# rev0.net
KiCad netlist of a schematic drawn in EAGLE
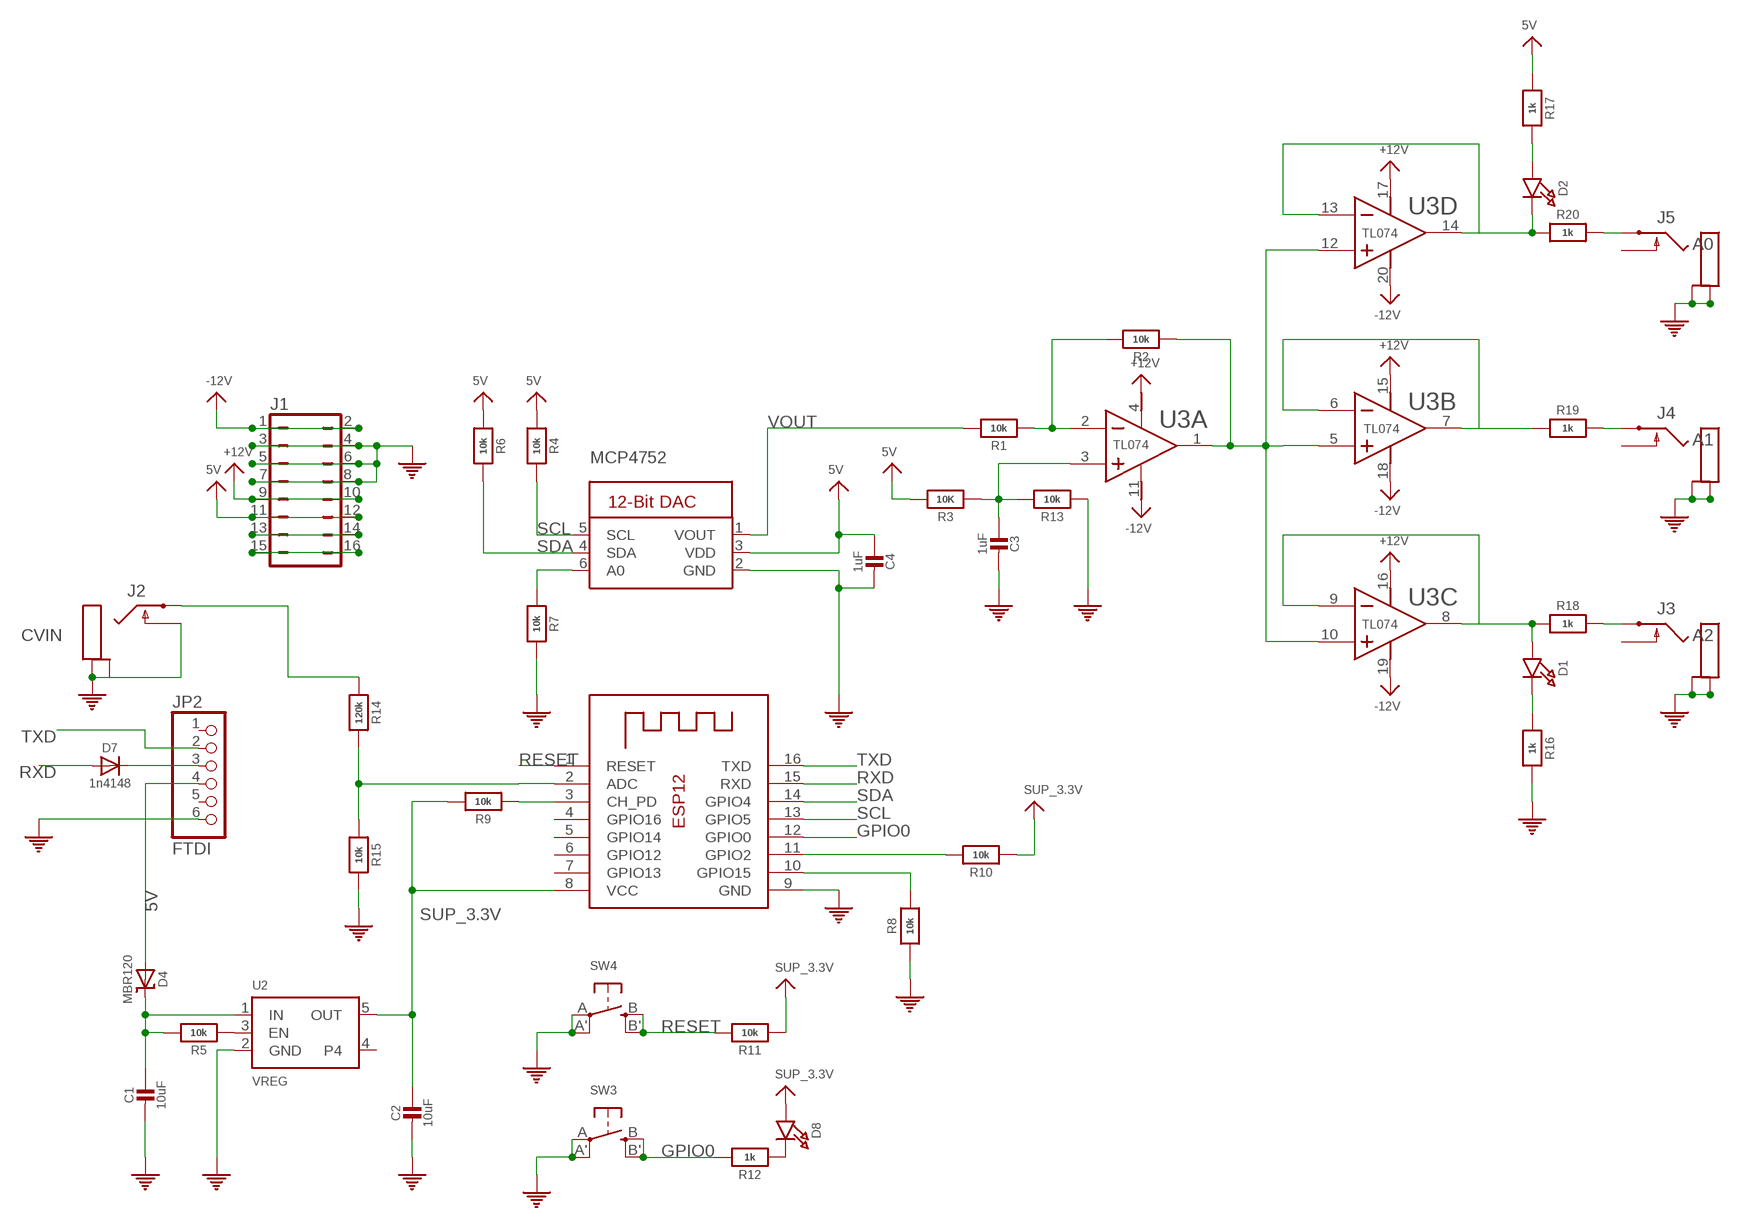
[diagram p0: schematic, sheet 1]

(export (version "E")
  (design (tool "Eeschema 10.0.6"))
  (components
    (comp (ref "C1")
      (value "10uF")
      (footprint "eagle-import:0805-NO")
      (libsource (lib "eagle-import") (part "CAP_CERAMIC0805-NOOUTLINE"))
    )
    (comp (ref "C2")
      (value "10uF")
      (footprint "eagle-import:0805-NO")
      (libsource (lib "eagle-import") (part "CAP_CERAMIC0805-NOOUTLINE"))
    )
    (comp (ref "C3")
      (value "1uF")
      (footprint "eagle-import:0805")
      (libsource (lib "eagle-import") (part "CAP_CERAMIC_0805"))
    )
    (comp (ref "C4")
      (value "1uF")
      (footprint "eagle-import:0805")
      (libsource (lib "eagle-import") (part "CAP_CERAMIC_0805"))
    )
    (comp (ref "D1")
      (value "LED0805_NOOUTLINE")
      (footprint "eagle-import:CHIPLED_0805_NOOUTLINE")
      (libsource (lib "eagle-import") (part "LED0805_NOOUTLINE"))
    )
    (comp (ref "D2")
      (value "LED0805_NOOUTLINE")
      (footprint "eagle-import:CHIPLED_0805_NOOUTLINE")
      (libsource (lib "eagle-import") (part "LED0805_NOOUTLINE"))
    )
    (comp (ref "D4")
      (value "MBR120")
      (footprint "eagle-import:SOD-123")
      (libsource (lib "eagle-import") (part "DIODE-SCHOTTKYSOD-123"))
    )
    (comp (ref "D7")
      (value "1n4148")
      (footprint "eagle-import:SOD-323")
      (libsource (lib "eagle-import") (part "DIODESOD-323"))
    )
    (comp (ref "D8")
      (value "LED0805_NOOUTLINE")
      (footprint "eagle-import:CHIPLED_0805_NOOUTLINE")
      (libsource (lib "eagle-import") (part "LED0805_NOOUTLINE"))
    )
    (comp (ref "J1")
      (value "JMP/16P/DIPDIP")
      (footprint "eagle-import:JMP_16P_DIP")
      (libsource (lib "eagle-import") (part "JMP/16P/DIPDIP"))
    )
    (comp (ref "J2")
      (value "1/8\"JACK/MONO/SWITCHED")
      (footprint "eagle-import:1_8_JACK_MONO_ERTHENVAR")
      (libsource (lib "eagle-import") (part "1/8{dblquote}JACK/MONO/SWITCHED"))
    )
    (comp (ref "J3")
      (value "1/8\"JACK/MONO/SWITCHED")
      (footprint "eagle-import:1_8_JACK_MONO_ERTHENVAR")
      (libsource (lib "eagle-import") (part "1/8{dblquote}JACK/MONO/SWITCHED"))
    )
    (comp (ref "J4")
      (value "1/8\"JACK/MONO/SWITCHED")
      (footprint "eagle-import:1_8_JACK_MONO_ERTHENVAR")
      (libsource (lib "eagle-import") (part "1/8{dblquote}JACK/MONO/SWITCHED"))
    )
    (comp (ref "J5")
      (value "1/8\"JACK/MONO/SWITCHED")
      (footprint "eagle-import:1_8_JACK_MONO_ERTHENVAR")
      (libsource (lib "eagle-import") (part "1/8{dblquote}JACK/MONO/SWITCHED"))
    )
    (comp (ref "JP2")
      (value "FTDI")
      (footprint "eagle-import:1X06_ROUND_70")
      (libsource (lib "eagle-import") (part "HEADER-1X670MIL"))
    )
    (comp (ref "MCP4752")
      (value "DAC_MCP4725")
      (footprint "eagle-import:SOT23-6")
      (libsource (lib "eagle-import") (part "DAC_MCP4725"))
    )
    (comp (ref "R1")
      (value "10k")
      (footprint "eagle-import:0805-NO")
      (libsource (lib "eagle-import") (part "RESISTOR0805_NOOUTLINE"))
    )
    (comp (ref "R2")
      (value "10k")
      (footprint "eagle-import:0805-NO")
      (libsource (lib "eagle-import") (part "RESISTOR0805_NOOUTLINE"))
    )
    (comp (ref "R3")
      (value "10K")
      (footprint "eagle-import:0805-NO")
      (libsource (lib "eagle-import") (part "RESISTOR0805_NOOUTLINE"))
    )
    (comp (ref "R4")
      (value "10k")
      (footprint "eagle-import:0805-NO")
      (libsource (lib "eagle-import") (part "RESISTOR0805_NOOUTLINE"))
    )
    (comp (ref "R5")
      (value "10k")
      (footprint "eagle-import:0805-NO")
      (libsource (lib "eagle-import") (part "RESISTOR0805_NOOUTLINE"))
    )
    (comp (ref "R6")
      (value "10k")
      (footprint "eagle-import:0805-NO")
      (libsource (lib "eagle-import") (part "RESISTOR0805_NOOUTLINE"))
    )
    (comp (ref "R7")
      (value "10k")
      (footprint "eagle-import:0805-NO")
      (libsource (lib "eagle-import") (part "RESISTOR0805_NOOUTLINE"))
    )
    (comp (ref "R8")
      (value "10k")
      (footprint "eagle-import:0805-NO")
      (libsource (lib "eagle-import") (part "RESISTOR0805_NOOUTLINE"))
    )
    (comp (ref "R9")
      (value "10k")
      (footprint "eagle-import:0805-NO")
      (libsource (lib "eagle-import") (part "RESISTOR0805_NOOUTLINE"))
    )
    (comp (ref "R10")
      (value "10k")
      (footprint "eagle-import:0805-NO")
      (libsource (lib "eagle-import") (part "RESISTOR0805_NOOUTLINE"))
    )
    (comp (ref "R11")
      (value "10k")
      (footprint "eagle-import:0805-NO")
      (libsource (lib "eagle-import") (part "RESISTOR0805_NOOUTLINE"))
    )
    (comp (ref "R12")
      (value "1k")
      (footprint "eagle-import:0805-NO")
      (libsource (lib "eagle-import") (part "RESISTOR0805_NOOUTLINE"))
    )
    (comp (ref "R13")
      (value "10k")
      (footprint "eagle-import:0805-NO")
      (libsource (lib "eagle-import") (part "RESISTOR0805_NOOUTLINE"))
    )
    (comp (ref "R14")
      (value "120k")
      (footprint "eagle-import:0805-NO")
      (libsource (lib "eagle-import") (part "RESISTOR0805_NOOUTLINE"))
    )
    (comp (ref "R15")
      (value "10k")
      (footprint "eagle-import:0805-NO")
      (libsource (lib "eagle-import") (part "RESISTOR0805_NOOUTLINE"))
    )
    (comp (ref "R16")
      (value "1k")
      (footprint "eagle-import:0805-NO")
      (libsource (lib "eagle-import") (part "RESISTOR0805_NOOUTLINE"))
    )
    (comp (ref "R17")
      (value "1k")
      (footprint "eagle-import:0805-NO")
      (libsource (lib "eagle-import") (part "RESISTOR0805_NOOUTLINE"))
    )
    (comp (ref "R18")
      (value "1k")
      (footprint "eagle-import:0805-NO")
      (libsource (lib "eagle-import") (part "RESISTOR0805_NOOUTLINE"))
    )
    (comp (ref "R19")
      (value "1k")
      (footprint "eagle-import:0805-NO")
      (libsource (lib "eagle-import") (part "RESISTOR0805_NOOUTLINE"))
    )
    (comp (ref "R20")
      (value "1k")
      (footprint "eagle-import:0805-NO")
      (libsource (lib "eagle-import") (part "RESISTOR0805_NOOUTLINE"))
    )
    (comp (ref "SW3")
      (value "SWITCH_TACT_SMT4.6X2.8")
      (footprint "eagle-import:BTN_KMR2_4.6X2.8")
      (libsource (lib "eagle-import") (part "SWITCH_TACT_SMT4.6X2.8"))
    )
    (comp (ref "SW4")
      (value "SWITCH_TACT_SMT4.6X2.8")
      (footprint "eagle-import:BTN_KMR2_4.6X2.8")
      (libsource (lib "eagle-import") (part "SWITCH_TACT_SMT4.6X2.8"))
    )
    (comp (ref "U2")
      (value "VREG")
      (footprint "eagle-import:SOT23-5")
      (libsource (lib "eagle-import") (part "VREG_SOT23-5"))
    )
    (comp (ref "U3")
      (value "TEXAS_INSTRUMENTS_TL074CDRTEXAS_INSTRUMENTS_TL074CDR_0_0")
      (footprint "eagle-import:TEXAS_INSTRUMENTS_TL074CDR_0")
      (fields (field (name "MF") "Texas Instruments") (field (name "MPN") "TL074CDR"))
      (libsource (lib "eagle-import") (part "TEXAS_INSTRUMENTS_TL074CDRTEXAS_INSTRUMENTS_TL074CDR_0_0"))
    )
    (comp (ref "X1")
      (value "ESP-12")
      (footprint "eagle-import:ESP-12")
      (libsource (lib "eagle-import") (part "ESP-12"))
    )
  )
  (nets
    (net (code "1") (name "+12V") (class "Default")
      (node (ref "J1") (pin "10") (pinfunction "10_10") (pintype "passive"))
      (node (ref "J1") (pin "9") (pinfunction "9_9") (pintype "passive"))
      (node (ref "U3") (pin "15") (pinfunction "VCC+_15") (pintype "power_in"))
      (node (ref "U3") (pin "16") (pinfunction "VCC+_16") (pintype "power_in"))
      (node (ref "U3") (pin "17") (pinfunction "VCC+_17") (pintype "power_in"))
      (node (ref "U3") (pin "4") (pinfunction "VCC+_4") (pintype "power_in"))
    )
    (net (code "2") (name "-12V") (class "Default")
      (node (ref "J1") (pin "1") (pinfunction "1_1") (pintype "passive"))
      (node (ref "J1") (pin "2") (pinfunction "2_2") (pintype "passive"))
      (node (ref "U3") (pin "11") (pinfunction "VCC-_11") (pintype "power_in"))
      (node (ref "U3") (pin "18") (pinfunction "VCC-_18") (pintype "power_in"))
      (node (ref "U3") (pin "19") (pinfunction "VCC-_19") (pintype "power_in"))
      (node (ref "U3") (pin "20") (pinfunction "VCC-_20") (pintype "power_in"))
    )
    (net (code "3") (name "/A0") (class "Default")
      (node (ref "D2") (pin "C") (pinfunction "C_C") (pintype "passive"))
      (node (ref "R20") (pin "1") (pinfunction "1_1") (pintype "passive"))
      (node (ref "U3") (pin "13") (pinfunction "IN4-_13") (pintype "input"))
      (node (ref "U3") (pin "14") (pinfunction "OUT4_14") (pintype "output"))
    )
    (net (code "4") (name "/A1") (class "Default")
      (node (ref "R19") (pin "1") (pinfunction "1_1") (pintype "passive"))
      (node (ref "U3") (pin "6") (pinfunction "IN2-_6") (pintype "input"))
      (node (ref "U3") (pin "7") (pinfunction "OUT2_7") (pintype "output"))
    )
    (net (code "5") (name "/A2") (class "Default")
      (node (ref "D1") (pin "A") (pinfunction "A_A") (pintype "passive"))
      (node (ref "R18") (pin "1") (pinfunction "1_1") (pintype "passive"))
      (node (ref "U3") (pin "8") (pinfunction "OUT3_8") (pintype "output"))
      (node (ref "U3") (pin "9") (pinfunction "IN3-_9") (pintype "input"))
    )
    (net (code "6") (name "/CVIN") (class "Default")
      (node (ref "J2") (pin "P$1") (pinfunction "5_P$1") (pintype "passive"))
      (node (ref "R14") (pin "1") (pinfunction "1_1") (pintype "passive"))
    )
    (net (code "7") (name "/CVOUT") (class "Default")
      (node (ref "R2") (pin "1") (pinfunction "1_1") (pintype "passive"))
      (node (ref "U3") (pin "1") (pinfunction "OUT1_1") (pintype "output"))
      (node (ref "U3") (pin "10") (pinfunction "IN3+_10") (pintype "input"))
      (node (ref "U3") (pin "12") (pinfunction "IN4+_12") (pintype "input"))
      (node (ref "U3") (pin "5") (pinfunction "IN2+_5") (pintype "input"))
    )
    (net (code "8") (name "/GPIO0") (class "Default")
      (node (ref "R12") (pin "2") (pinfunction "2_2") (pintype "passive"))
      (node (ref "SW3") (pin "B") (pinfunction "S_B") (pintype "passive"))
      (node (ref "SW3") (pin "B'") (pinfunction "S1_B'") (pintype "passive"))
      (node (ref "X1") (pin "12") (pinfunction "GPIO0_12") (pintype "bidirectional"))
    )
    (net (code "9") (name "/I0") (class "Default")
      (node (ref "R14") (pin "2") (pinfunction "2_2") (pintype "passive"))
      (node (ref "R15") (pin "1") (pinfunction "1_1") (pintype "passive"))
      (node (ref "X1") (pin "2") (pinfunction "ADC_2") (pintype "passive"))
    )
    (net (code "10") (name "/RESET") (class "Default")
      (node (ref "R11") (pin "2") (pinfunction "2_2") (pintype "passive"))
      (node (ref "SW4") (pin "B") (pinfunction "S_B") (pintype "passive"))
      (node (ref "SW4") (pin "B'") (pinfunction "S1_B'") (pintype "passive"))
      (node (ref "X1") (pin "1") (pinfunction "RESET_1") (pintype "input"))
    )
    (net (code "11") (name "/RXD") (class "Default")
      (node (ref "D7") (pin "A") (pinfunction "A_A") (pintype "passive"))
      (node (ref "X1") (pin "15") (pinfunction "RXD_15") (pintype "input"))
    )
    (net (code "12") (name "/SCL") (class "Default")
      (node (ref "MCP4752") (pin "5") (pinfunction "SCL_5") (pintype "bidirectional"))
      (node (ref "R4") (pin "2") (pinfunction "2_2") (pintype "passive"))
      (node (ref "X1") (pin "13") (pinfunction "GPIO5_13") (pintype "bidirectional"))
    )
    (net (code "13") (name "/SDA") (class "Default")
      (node (ref "MCP4752") (pin "4") (pinfunction "SDA_4") (pintype "bidirectional"))
      (node (ref "R6") (pin "2") (pinfunction "2_2") (pintype "passive"))
      (node (ref "X1") (pin "14") (pinfunction "GPIO4_14") (pintype "bidirectional"))
    )
    (net (code "14") (name "/TXD") (class "Default")
      (node (ref "JP2") (pin "2") (pinfunction "2_2") (pintype "passive"))
      (node (ref "X1") (pin "16") (pinfunction "TXD_16") (pintype "output"))
    )
    (net (code "15") (name "/VOUT") (class "Default")
      (node (ref "MCP4752") (pin "1") (pinfunction "VOUT_1") (pintype "output"))
      (node (ref "R1") (pin "2") (pinfunction "2_2") (pintype "passive"))
    )
    (net (code "16") (name "5V") (class "Default")
      (node (ref "C4") (pin "1") (pinfunction "1_1") (pintype "passive"))
      (node (ref "D4") (pin "A") (pinfunction "A_A") (pintype "passive"))
      (node (ref "J1") (pin "11") (pinfunction "11_11") (pintype "passive"))
      (node (ref "J1") (pin "12") (pinfunction "12_12") (pintype "passive"))
      (node (ref "JP2") (pin "4") (pinfunction "4_4") (pintype "passive"))
      (node (ref "MCP4752") (pin "3") (pinfunction "VDD_3") (pintype "power_in"))
      (node (ref "R17") (pin "1") (pinfunction "1_1") (pintype "passive"))
      (node (ref "R3") (pin "2") (pinfunction "2_2") (pintype "passive"))
      (node (ref "R4") (pin "1") (pinfunction "1_1") (pintype "passive"))
      (node (ref "R6") (pin "1") (pinfunction "1_1") (pintype "passive"))
    )
    (net (code "17") (name "GND") (class "Default")
      (node (ref "C1") (pin "2") (pinfunction "2_2") (pintype "passive"))
      (node (ref "C2") (pin "2") (pinfunction "2_2") (pintype "passive"))
      (node (ref "C3") (pin "2") (pinfunction "2_2") (pintype "passive"))
      (node (ref "C4") (pin "2") (pinfunction "2_2") (pintype "passive"))
      (node (ref "J1") (pin "3") (pinfunction "3_3") (pintype "passive"))
      (node (ref "J1") (pin "4") (pinfunction "4_4") (pintype "passive"))
      (node (ref "J1") (pin "5") (pinfunction "5_5") (pintype "passive"))
      (node (ref "J1") (pin "6") (pinfunction "6_6") (pintype "passive"))
      (node (ref "J1") (pin "7") (pinfunction "7_7") (pintype "passive"))
      (node (ref "J1") (pin "8") (pinfunction "8_8") (pintype "passive"))
      (node (ref "J2") (pin "P$2") (pinfunction "4_P$2") (pintype "passive"))
      (node (ref "J2") (pin "P$3") (pinfunction "1_P$3") (pintype "passive"))
      (node (ref "J2") (pin "P$4") (pinfunction "P$1_P$4") (pintype "bidirectional"))
      (node (ref "J3") (pin "P$3") (pinfunction "1_P$3") (pintype "passive"))
      (node (ref "J3") (pin "P$4") (pinfunction "P$1_P$4") (pintype "bidirectional"))
      (node (ref "J4") (pin "P$3") (pinfunction "1_P$3") (pintype "passive"))
      (node (ref "J4") (pin "P$4") (pinfunction "P$1_P$4") (pintype "bidirectional"))
      (node (ref "J5") (pin "P$3") (pinfunction "1_P$3") (pintype "passive"))
      (node (ref "J5") (pin "P$4") (pinfunction "P$1_P$4") (pintype "bidirectional"))
      (node (ref "JP2") (pin "6") (pinfunction "6_6") (pintype "passive"))
      (node (ref "MCP4752") (pin "2") (pinfunction "GND_2") (pintype "power_in"))
      (node (ref "R13") (pin "1") (pinfunction "1_1") (pintype "passive"))
      (node (ref "R15") (pin "2") (pinfunction "2_2") (pintype "passive"))
      (node (ref "R16") (pin "2") (pinfunction "2_2") (pintype "passive"))
      (node (ref "R7") (pin "2") (pinfunction "2_2") (pintype "passive"))
      (node (ref "R8") (pin "1") (pinfunction "1_1") (pintype "passive"))
      (node (ref "SW3") (pin "A") (pinfunction "P_A") (pintype "passive"))
      (node (ref "SW3") (pin "A'") (pinfunction "P1_A'") (pintype "passive"))
      (node (ref "SW4") (pin "A") (pinfunction "P_A") (pintype "passive"))
      (node (ref "SW4") (pin "A'") (pinfunction "P1_A'") (pintype "passive"))
      (node (ref "U2") (pin "2") (pinfunction "GND_2") (pintype "power_in"))
      (node (ref "X1") (pin "9") (pinfunction "GND_9") (pintype "power_in"))
    )
    (net (code "18") (name "Net-(D1-PadC)") (class "Default")
      (node (ref "D1") (pin "C") (pinfunction "C_C") (pintype "passive"))
      (node (ref "R16") (pin "1") (pinfunction "1_1") (pintype "passive"))
    )
    (net (code "19") (name "Net-(D2-PadA)") (class "Default")
      (node (ref "D2") (pin "A") (pinfunction "A_A") (pintype "passive"))
      (node (ref "R17") (pin "2") (pinfunction "2_2") (pintype "passive"))
    )
    (net (code "20") (name "Net-(D7-PadC)") (class "Default")
      (node (ref "D7") (pin "C") (pinfunction "C_C") (pintype "passive"))
      (node (ref "JP2") (pin "3") (pinfunction "3_3") (pintype "passive"))
    )
    (net (code "21") (name "Net-(D8-PadC)") (class "Default")
      (node (ref "D8") (pin "C") (pinfunction "C_C") (pintype "passive"))
      (node (ref "R12") (pin "1") (pinfunction "1_1") (pintype "passive"))
    )
    (net (code "22") (name "Net-(J1-Pad13)") (class "Default")
      (node (ref "J1") (pin "13") (pinfunction "13_13") (pintype "passive"))
      (node (ref "J1") (pin "14") (pinfunction "14_14") (pintype "passive"))
    )
    (net (code "23") (name "Net-(J1-Pad15)") (class "Default")
      (node (ref "J1") (pin "15") (pinfunction "15_15") (pintype "passive"))
      (node (ref "J1") (pin "16") (pinfunction "16_16") (pintype "passive"))
    )
    (net (code "24") (name "Net-(J3-5)") (class "Default")
      (node (ref "J3") (pin "P$1") (pinfunction "5_P$1") (pintype "passive"))
      (node (ref "R18") (pin "2") (pinfunction "2_2") (pintype "passive"))
    )
    (net (code "25") (name "Net-(J4-5)") (class "Default")
      (node (ref "J4") (pin "P$1") (pinfunction "5_P$1") (pintype "passive"))
      (node (ref "R19") (pin "2") (pinfunction "2_2") (pintype "passive"))
    )
    (net (code "26") (name "Net-(J5-5)") (class "Default")
      (node (ref "J5") (pin "P$1") (pinfunction "5_P$1") (pintype "passive"))
      (node (ref "R20") (pin "2") (pinfunction "2_2") (pintype "passive"))
    )
    (net (code "27") (name "Net-(MCP4752-A0)") (class "Default")
      (node (ref "MCP4752") (pin "6") (pinfunction "A0_6") (pintype "input"))
      (node (ref "R7") (pin "1") (pinfunction "1_1") (pintype "passive"))
    )
    (net (code "28") (name "Net-(U2-EN)") (class "Default")
      (node (ref "R5") (pin "1") (pinfunction "1_1") (pintype "passive"))
      (node (ref "U2") (pin "3") (pinfunction "EN_3") (pintype "input"))
    )
    (net (code "29") (name "Net-(U2-IN)") (class "Default")
      (node (ref "C1") (pin "1") (pinfunction "1_1") (pintype "passive"))
      (node (ref "D4") (pin "C") (pinfunction "C_C") (pintype "passive"))
      (node (ref "R5") (pin "2") (pinfunction "2_2") (pintype "passive"))
      (node (ref "U2") (pin "1") (pinfunction "IN_1") (pintype "power_in"))
    )
    (net (code "30") (name "Net-(U3A-IN1+)") (class "Default")
      (node (ref "C3") (pin "1") (pinfunction "1_1") (pintype "passive"))
      (node (ref "R13") (pin "2") (pinfunction "2_2") (pintype "passive"))
      (node (ref "R3") (pin "1") (pinfunction "1_1") (pintype "passive"))
      (node (ref "U3") (pin "3") (pinfunction "IN1+_3") (pintype "input"))
    )
    (net (code "31") (name "Net-(U3A-IN1-)") (class "Default")
      (node (ref "R1") (pin "1") (pinfunction "1_1") (pintype "passive"))
      (node (ref "R2") (pin "2") (pinfunction "2_2") (pintype "passive"))
      (node (ref "U3") (pin "2") (pinfunction "IN1-_2") (pintype "input"))
    )
    (net (code "32") (name "Net-(X1-CH_PD)") (class "Default")
      (node (ref "R9") (pin "1") (pinfunction "1_1") (pintype "passive"))
      (node (ref "X1") (pin "3") (pinfunction "CH_PD_3") (pintype "input"))
    )
    (net (code "33") (name "Net-(X1-GPIO2)") (class "Default")
      (node (ref "R10") (pin "2") (pinfunction "2_2") (pintype "passive"))
      (node (ref "X1") (pin "11") (pinfunction "GPIO2_11") (pintype "bidirectional"))
    )
    (net (code "34") (name "Net-(X1-GPIO15)") (class "Default")
      (node (ref "R8") (pin "2") (pinfunction "2_2") (pintype "passive"))
      (node (ref "X1") (pin "10") (pinfunction "GPIO15_10") (pintype "bidirectional"))
    )
    (net (code "35") (name "SUP_3.3V") (class "Default")
      (node (ref "C2") (pin "1") (pinfunction "1_1") (pintype "passive"))
      (node (ref "D8") (pin "A") (pinfunction "A_A") (pintype "passive"))
      (node (ref "R10") (pin "1") (pinfunction "1_1") (pintype "passive"))
      (node (ref "R11") (pin "1") (pinfunction "1_1") (pintype "passive"))
      (node (ref "R9") (pin "2") (pinfunction "2_2") (pintype "passive"))
      (node (ref "U2") (pin "5") (pinfunction "OUT_5") (pintype "power_in"))
      (node (ref "X1") (pin "8") (pinfunction "VCC_8") (pintype "power_in"))
    )
    (net (code "36") (name "unconnected-(J3-4-PadP$2)") (class "Default")
      (node (ref "J3") (pin "P$2") (pinfunction "4_P$2") (pintype "passive"))
    )
    (net (code "37") (name "unconnected-(J4-4-PadP$2)") (class "Default")
      (node (ref "J4") (pin "P$2") (pinfunction "4_P$2") (pintype "passive"))
    )
    (net (code "38") (name "unconnected-(J5-4-PadP$2)") (class "Default")
      (node (ref "J5") (pin "P$2") (pinfunction "4_P$2") (pintype "passive"))
    )
    (net (code "39") (name "unconnected-(JP2-Pad1)") (class "Default")
      (node (ref "JP2") (pin "1") (pinfunction "1_1") (pintype "passive"))
    )
    (net (code "40") (name "unconnected-(JP2-Pad5)") (class "Default")
      (node (ref "JP2") (pin "5") (pinfunction "5_5") (pintype "passive"))
    )
    (net (code "41") (name "unconnected-(U2-P4-Pad4)") (class "Default")
      (node (ref "U2") (pin "4") (pinfunction "P4_4") (pintype "bidirectional"))
    )
    (net (code "42") (name "unconnected-(X1-GPIO12-Pad6)") (class "Default")
      (node (ref "X1") (pin "6") (pinfunction "GPIO12_6") (pintype "bidirectional"))
    )
    (net (code "43") (name "unconnected-(X1-GPIO13-Pad7)") (class "Default")
      (node (ref "X1") (pin "7") (pinfunction "GPIO13_7") (pintype "bidirectional"))
    )
    (net (code "44") (name "unconnected-(X1-GPIO14-Pad5)") (class "Default")
      (node (ref "X1") (pin "5") (pinfunction "GPIO14_5") (pintype "bidirectional"))
    )
    (net (code "45") (name "unconnected-(X1-GPIO16-Pad4)") (class "Default")
      (node (ref "X1") (pin "4") (pinfunction "GPIO16_4") (pintype "bidirectional"))
    )
  )
)
